# snes_ext_port_adapter.net
KiCad netlist of a schematic drawn in EAGLE
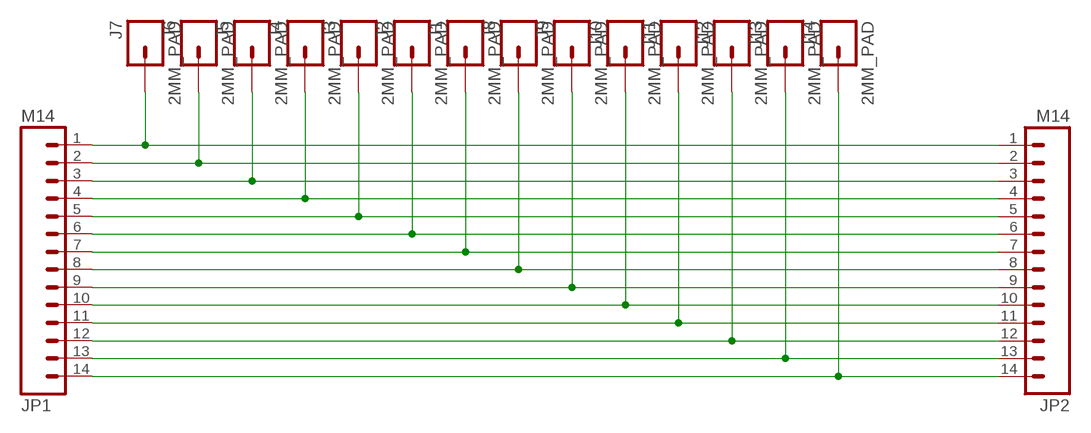
[diagram p0: schematic, sheet 1]

(export (version "E")
  (design (tool "Eeschema 10.0.6"))
  (components
    (comp (ref "J1")
      (value "2MM_PAD")
      (footprint "eagle-import:1MM_PAD")
      (libsource (lib "eagle-import") (part "2MM_PAD"))
    )
    (comp (ref "J2")
      (value "2MM_PAD")
      (footprint "eagle-import:1MM_PAD")
      (libsource (lib "eagle-import") (part "2MM_PAD"))
    )
    (comp (ref "J3")
      (value "2MM_PAD")
      (footprint "eagle-import:1MM_PAD")
      (libsource (lib "eagle-import") (part "2MM_PAD"))
    )
    (comp (ref "J4")
      (value "2MM_PAD")
      (footprint "eagle-import:1MM_PAD")
      (libsource (lib "eagle-import") (part "2MM_PAD"))
    )
    (comp (ref "J5")
      (value "2MM_PAD")
      (footprint "eagle-import:1MM_PAD")
      (libsource (lib "eagle-import") (part "2MM_PAD"))
    )
    (comp (ref "J6")
      (value "2MM_PAD")
      (footprint "eagle-import:1MM_PAD")
      (libsource (lib "eagle-import") (part "2MM_PAD"))
    )
    (comp (ref "J7")
      (value "2MM_PAD")
      (footprint "eagle-import:1MM_PAD")
      (libsource (lib "eagle-import") (part "2MM_PAD"))
    )
    (comp (ref "J8")
      (value "2MM_PAD")
      (footprint "eagle-import:1MM_PAD")
      (libsource (lib "eagle-import") (part "2MM_PAD"))
    )
    (comp (ref "J9")
      (value "2MM_PAD")
      (footprint "eagle-import:1MM_PAD")
      (libsource (lib "eagle-import") (part "2MM_PAD"))
    )
    (comp (ref "J10")
      (value "2MM_PAD")
      (footprint "eagle-import:1MM_PAD")
      (libsource (lib "eagle-import") (part "2MM_PAD"))
    )
    (comp (ref "J11")
      (value "2MM_PAD")
      (footprint "eagle-import:1MM_PAD")
      (libsource (lib "eagle-import") (part "2MM_PAD"))
    )
    (comp (ref "J12")
      (value "2MM_PAD")
      (footprint "eagle-import:1MM_PAD")
      (libsource (lib "eagle-import") (part "2MM_PAD"))
    )
    (comp (ref "J13")
      (value "2MM_PAD")
      (footprint "eagle-import:1MM_PAD")
      (libsource (lib "eagle-import") (part "2MM_PAD"))
    )
    (comp (ref "J14")
      (value "2MM_PAD")
      (footprint "eagle-import:1MM_PAD")
      (libsource (lib "eagle-import") (part "2MM_PAD"))
    )
    (comp (ref "JP1")
      (value "M14")
      (footprint "eagle-import:1X14")
      (libsource (lib "eagle-import") (part "M14"))
    )
    (comp (ref "JP2")
      (value "M14")
      (footprint "eagle-import:1X14")
      (libsource (lib "eagle-import") (part "M14"))
    )
  )
  (nets
    (net (code "1") (name "Net-(J1-1)") (class "Default")
      (node (ref "J1") (pin "P$1") (pinfunction "1_P$1") (pintype "passive"))
      (node (ref "JP1") (pin "7") (pinfunction "7_7") (pintype "passive"))
      (node (ref "JP2") (pin "7") (pinfunction "7_7") (pintype "passive"))
    )
    (net (code "2") (name "Net-(J2-1)") (class "Default")
      (node (ref "J2") (pin "P$1") (pinfunction "1_P$1") (pintype "passive"))
      (node (ref "JP1") (pin "6") (pinfunction "6_6") (pintype "passive"))
      (node (ref "JP2") (pin "6") (pinfunction "6_6") (pintype "passive"))
    )
    (net (code "3") (name "Net-(J3-1)") (class "Default")
      (node (ref "J3") (pin "P$1") (pinfunction "1_P$1") (pintype "passive"))
      (node (ref "JP1") (pin "5") (pinfunction "5_5") (pintype "passive"))
      (node (ref "JP2") (pin "5") (pinfunction "5_5") (pintype "passive"))
    )
    (net (code "4") (name "Net-(J4-1)") (class "Default")
      (node (ref "J4") (pin "P$1") (pinfunction "1_P$1") (pintype "passive"))
      (node (ref "JP1") (pin "4") (pinfunction "4_4") (pintype "passive"))
      (node (ref "JP2") (pin "4") (pinfunction "4_4") (pintype "passive"))
    )
    (net (code "5") (name "Net-(J5-1)") (class "Default")
      (node (ref "J5") (pin "P$1") (pinfunction "1_P$1") (pintype "passive"))
      (node (ref "JP1") (pin "3") (pinfunction "3_3") (pintype "passive"))
      (node (ref "JP2") (pin "3") (pinfunction "3_3") (pintype "passive"))
    )
    (net (code "6") (name "Net-(J6-1)") (class "Default")
      (node (ref "J6") (pin "P$1") (pinfunction "1_P$1") (pintype "passive"))
      (node (ref "JP1") (pin "2") (pinfunction "2_2") (pintype "passive"))
      (node (ref "JP2") (pin "2") (pinfunction "2_2") (pintype "passive"))
    )
    (net (code "7") (name "Net-(J7-1)") (class "Default")
      (node (ref "J7") (pin "P$1") (pinfunction "1_P$1") (pintype "passive"))
      (node (ref "JP1") (pin "1") (pinfunction "1_1") (pintype "passive"))
      (node (ref "JP2") (pin "1") (pinfunction "1_1") (pintype "passive"))
    )
    (net (code "8") (name "Net-(J8-1)") (class "Default")
      (node (ref "J8") (pin "P$1") (pinfunction "1_P$1") (pintype "passive"))
      (node (ref "JP1") (pin "8") (pinfunction "8_8") (pintype "passive"))
      (node (ref "JP2") (pin "8") (pinfunction "8_8") (pintype "passive"))
    )
    (net (code "9") (name "Net-(J9-1)") (class "Default")
      (node (ref "J9") (pin "P$1") (pinfunction "1_P$1") (pintype "passive"))
      (node (ref "JP1") (pin "9") (pinfunction "9_9") (pintype "passive"))
      (node (ref "JP2") (pin "9") (pinfunction "9_9") (pintype "passive"))
    )
    (net (code "10") (name "Net-(J10-1)") (class "Default")
      (node (ref "J10") (pin "P$1") (pinfunction "1_P$1") (pintype "passive"))
      (node (ref "JP1") (pin "10") (pinfunction "10_10") (pintype "passive"))
      (node (ref "JP2") (pin "10") (pinfunction "10_10") (pintype "passive"))
    )
    (net (code "11") (name "Net-(J11-1)") (class "Default")
      (node (ref "J11") (pin "P$1") (pinfunction "1_P$1") (pintype "passive"))
      (node (ref "JP1") (pin "11") (pinfunction "11_11") (pintype "passive"))
      (node (ref "JP2") (pin "11") (pinfunction "11_11") (pintype "passive"))
    )
    (net (code "12") (name "Net-(J12-1)") (class "Default")
      (node (ref "J12") (pin "P$1") (pinfunction "1_P$1") (pintype "passive"))
      (node (ref "JP1") (pin "12") (pinfunction "12_12") (pintype "passive"))
      (node (ref "JP2") (pin "12") (pinfunction "12_12") (pintype "passive"))
    )
    (net (code "13") (name "Net-(J13-1)") (class "Default")
      (node (ref "J13") (pin "P$1") (pinfunction "1_P$1") (pintype "passive"))
      (node (ref "JP1") (pin "13") (pinfunction "13_13") (pintype "passive"))
      (node (ref "JP2") (pin "13") (pinfunction "13_13") (pintype "passive"))
    )
    (net (code "14") (name "Net-(J14-1)") (class "Default")
      (node (ref "J14") (pin "P$1") (pinfunction "1_P$1") (pintype "passive"))
      (node (ref "JP1") (pin "14") (pinfunction "14_14") (pintype "passive"))
      (node (ref "JP2") (pin "14") (pinfunction "14_14") (pintype "passive"))
    )
  )
)
